# Zynq_power_and_decoupling.net
KiCad netlist of a schematic drawn in Altium Designer
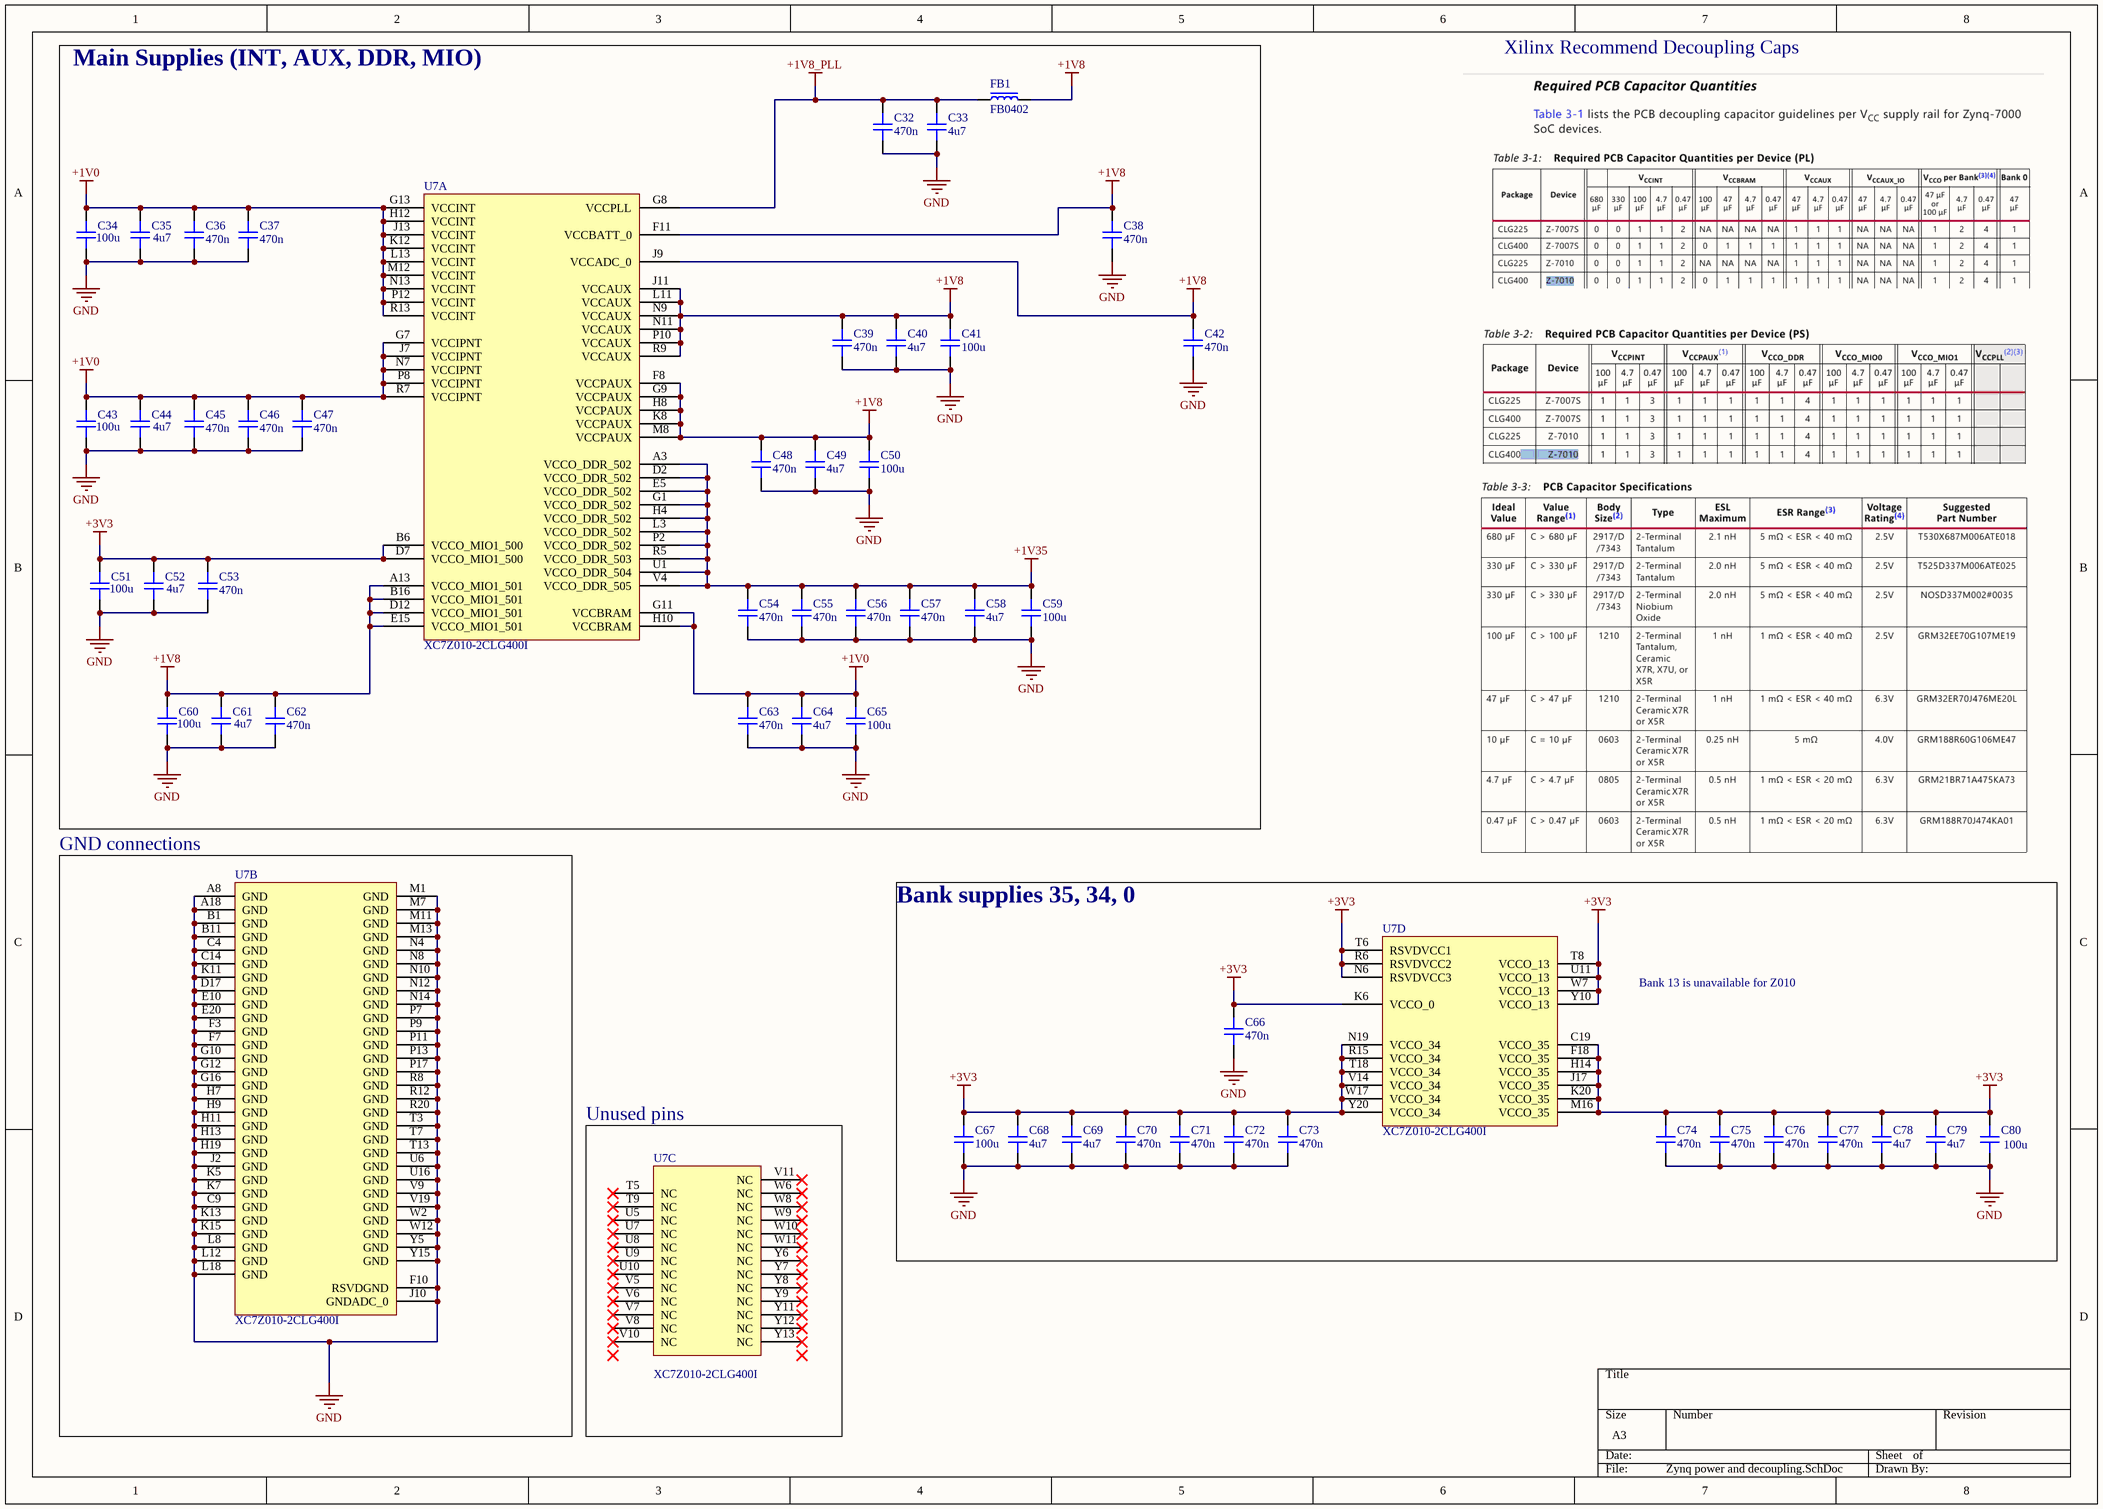
[diagram p0: Zynq power and decoupling.SchDoc]

(export (version "E")
  (design (tool "Eeschema 10.0.6"))
  (components
    (comp (ref "C32")
      (value "470n")
      (footprint "CAP_0201")
      (description "Capacitor SMD 0201")
      (fields (field (name "Comment") "C0201"))
      (libsource (lib "Schematic-Lib-PhilsLab") (part "CAP_0201"))
    )
    (comp (ref "C33")
      (value "4u7")
      (footprint "CAP_0402")
      (description "Capacitor SMD 0402")
      (fields (field (name "Comment") "C0402"))
      (libsource (lib "Schematic-Lib-PhilsLab") (part "CAP_0402"))
    )
    (comp (ref "C34")
      (value "100u")
      (footprint "CAP_1210")
      (description "Capacitor SMD 1210")
      (fields (field (name "Comment") "C1210"))
      (libsource (lib "Schematic-Lib-PhilsLab") (part "CAP_1210"))
    )
    (comp (ref "C35")
      (value "4u7")
      (footprint "CAP_0402")
      (description "Capacitor SMD 0402")
      (fields (field (name "Comment") "C0402"))
      (libsource (lib "Schematic-Lib-PhilsLab") (part "CAP_0402"))
    )
    (comp (ref "C36")
      (value "470n")
      (footprint "CAP_0201")
      (description "Capacitor SMD 0201")
      (fields (field (name "Comment") "C0201"))
      (libsource (lib "Schematic-Lib-PhilsLab") (part "CAP_0201"))
    )
    (comp (ref "C37")
      (value "470n")
      (footprint "CAP_0201")
      (description "Capacitor SMD 0201")
      (fields (field (name "Comment") "C0201"))
      (libsource (lib "Schematic-Lib-PhilsLab") (part "CAP_0201"))
    )
    (comp (ref "C38")
      (value "470n")
      (footprint "CAP_0201")
      (description "Capacitor SMD 0201")
      (fields (field (name "Comment") "C0201"))
      (libsource (lib "Schematic-Lib-PhilsLab") (part "CAP_0201"))
    )
    (comp (ref "C39")
      (value "470n")
      (footprint "CAP_0201")
      (description "Capacitor SMD 0201")
      (fields (field (name "Comment") "C0201"))
      (libsource (lib "Schematic-Lib-PhilsLab") (part "CAP_0201"))
    )
    (comp (ref "C40")
      (value "4u7")
      (footprint "CAP_0402")
      (description "Capacitor SMD 0402")
      (fields (field (name "Comment") "C0402"))
      (libsource (lib "Schematic-Lib-PhilsLab") (part "CAP_0402"))
    )
    (comp (ref "C41")
      (value "100u")
      (footprint "CAP_1210")
      (description "Capacitor SMD 1210")
      (fields (field (name "Comment") "C1210"))
      (libsource (lib "Schematic-Lib-PhilsLab") (part "CAP_1210"))
    )
    (comp (ref "C42")
      (value "470n")
      (footprint "CAP_0201")
      (description "Capacitor SMD 0201")
      (fields (field (name "Comment") "C0201"))
      (libsource (lib "Schematic-Lib-PhilsLab") (part "CAP_0201"))
    )
    (comp (ref "C43")
      (value "100u")
      (footprint "CAP_1210")
      (description "Capacitor SMD 1210")
      (fields (field (name "Comment") "C1210"))
      (libsource (lib "Schematic-Lib-PhilsLab") (part "CAP_1210"))
    )
    (comp (ref "C44")
      (value "4u7")
      (footprint "CAP_0402")
      (description "Capacitor SMD 0402")
      (fields (field (name "Comment") "C0402"))
      (libsource (lib "Schematic-Lib-PhilsLab") (part "CAP_0402"))
    )
    (comp (ref "C45")
      (value "470n")
      (footprint "CAP_0201")
      (description "Capacitor SMD 0201")
      (fields (field (name "Comment") "C0201"))
      (libsource (lib "Schematic-Lib-PhilsLab") (part "CAP_0201"))
    )
    (comp (ref "C46")
      (value "470n")
      (footprint "CAP_0201")
      (description "Capacitor SMD 0201")
      (fields (field (name "Comment") "C0201"))
      (libsource (lib "Schematic-Lib-PhilsLab") (part "CAP_0201"))
    )
    (comp (ref "C47")
      (value "470n")
      (footprint "CAP_0201")
      (description "Capacitor SMD 0201")
      (fields (field (name "Comment") "C0201"))
      (libsource (lib "Schematic-Lib-PhilsLab") (part "CAP_0201"))
    )
    (comp (ref "C48")
      (value "470n")
      (footprint "CAP_0201")
      (description "Capacitor SMD 0201")
      (fields (field (name "Comment") "C0201"))
      (libsource (lib "Schematic-Lib-PhilsLab") (part "CAP_0201"))
    )
    (comp (ref "C49")
      (value "4u7")
      (footprint "CAP_0402")
      (description "Capacitor SMD 0402")
      (fields (field (name "Comment") "C0402"))
      (libsource (lib "Schematic-Lib-PhilsLab") (part "CAP_0402"))
    )
    (comp (ref "C50")
      (value "100u")
      (footprint "CAP_1210")
      (description "Capacitor SMD 1210")
      (fields (field (name "Comment") "C1210"))
      (libsource (lib "Schematic-Lib-PhilsLab") (part "CAP_1210"))
    )
    (comp (ref "C51")
      (value "100u")
      (footprint "CAP_1210")
      (description "Capacitor SMD 1210")
      (fields (field (name "Comment") "C1210"))
      (libsource (lib "Schematic-Lib-PhilsLab") (part "CAP_1210"))
    )
    (comp (ref "C52")
      (value "4u7")
      (footprint "CAP_0402")
      (description "Capacitor SMD 0402")
      (fields (field (name "Comment") "C0402"))
      (libsource (lib "Schematic-Lib-PhilsLab") (part "CAP_0402"))
    )
    (comp (ref "C53")
      (value "470n")
      (footprint "CAP_0201")
      (description "Capacitor SMD 0201")
      (fields (field (name "Comment") "C0201"))
      (libsource (lib "Schematic-Lib-PhilsLab") (part "CAP_0201"))
    )
    (comp (ref "C54")
      (value "470n")
      (footprint "CAP_0201")
      (description "Capacitor SMD 0201")
      (fields (field (name "Comment") "C0201"))
      (libsource (lib "Schematic-Lib-PhilsLab") (part "CAP_0201"))
    )
    (comp (ref "C55")
      (value "470n")
      (footprint "CAP_0201")
      (description "Capacitor SMD 0201")
      (fields (field (name "Comment") "C0201"))
      (libsource (lib "Schematic-Lib-PhilsLab") (part "CAP_0201"))
    )
    (comp (ref "C56")
      (value "470n")
      (footprint "CAP_0201")
      (description "Capacitor SMD 0201")
      (fields (field (name "Comment") "C0201"))
      (libsource (lib "Schematic-Lib-PhilsLab") (part "CAP_0201"))
    )
    (comp (ref "C57")
      (value "470n")
      (footprint "CAP_0201")
      (description "Capacitor SMD 0201")
      (fields (field (name "Comment") "C0201"))
      (libsource (lib "Schematic-Lib-PhilsLab") (part "CAP_0201"))
    )
    (comp (ref "C58")
      (value "4u7")
      (footprint "CAP_0402")
      (description "Capacitor SMD 0402")
      (fields (field (name "Comment") "C0402"))
      (libsource (lib "Schematic-Lib-PhilsLab") (part "CAP_0402"))
    )
    (comp (ref "C59")
      (value "100u")
      (footprint "CAP_1210")
      (description "Capacitor SMD 1210")
      (fields (field (name "Comment") "C1210"))
      (libsource (lib "Schematic-Lib-PhilsLab") (part "CAP_1210"))
    )
    (comp (ref "C60")
      (value "100u")
      (footprint "CAP_1210")
      (description "Capacitor SMD 1210")
      (fields (field (name "Comment") "C1210"))
      (libsource (lib "Schematic-Lib-PhilsLab") (part "CAP_1210"))
    )
    (comp (ref "C61")
      (value "4u7")
      (footprint "CAP_0402")
      (description "Capacitor SMD 0402")
      (fields (field (name "Comment") "C0402"))
      (libsource (lib "Schematic-Lib-PhilsLab") (part "CAP_0402"))
    )
    (comp (ref "C62")
      (value "470n")
      (footprint "CAP_0201")
      (description "Capacitor SMD 0201")
      (fields (field (name "Comment") "C0201"))
      (libsource (lib "Schematic-Lib-PhilsLab") (part "CAP_0201"))
    )
    (comp (ref "C63")
      (value "470n")
      (footprint "CAP_0201")
      (description "Capacitor SMD 0201")
      (fields (field (name "Comment") "C0201"))
      (libsource (lib "Schematic-Lib-PhilsLab") (part "CAP_0201"))
    )
    (comp (ref "C64")
      (value "4u7")
      (footprint "CAP_0402")
      (description "Capacitor SMD 0402")
      (fields (field (name "Comment") "C0402"))
      (libsource (lib "Schematic-Lib-PhilsLab") (part "CAP_0402"))
    )
    (comp (ref "C65")
      (value "100u")
      (footprint "CAP_1210")
      (description "Capacitor SMD 1210")
      (fields (field (name "Comment") "C1210"))
      (libsource (lib "Schematic-Lib-PhilsLab") (part "CAP_1210"))
    )
    (comp (ref "C66")
      (value "470n")
      (footprint "CAP_0201")
      (description "Capacitor SMD 0201")
      (fields (field (name "Comment") "C0201"))
      (libsource (lib "Schematic-Lib-PhilsLab") (part "CAP_0201"))
    )
    (comp (ref "C67")
      (value "100u")
      (footprint "CAP_1210")
      (description "Capacitor SMD 1210")
      (fields (field (name "Comment") "C1210"))
      (libsource (lib "Schematic-Lib-PhilsLab") (part "CAP_1210"))
    )
    (comp (ref "C68")
      (value "4u7")
      (footprint "CAP_0402")
      (description "Capacitor SMD 0402")
      (fields (field (name "Comment") "C0402"))
      (libsource (lib "Schematic-Lib-PhilsLab") (part "CAP_0402"))
    )
    (comp (ref "C69")
      (value "4u7")
      (footprint "CAP_0402")
      (description "Capacitor SMD 0402")
      (fields (field (name "Comment") "C0402"))
      (libsource (lib "Schematic-Lib-PhilsLab") (part "CAP_0402"))
    )
    (comp (ref "C70")
      (value "470n")
      (footprint "CAP_0201")
      (description "Capacitor SMD 0201")
      (fields (field (name "Comment") "C0201"))
      (libsource (lib "Schematic-Lib-PhilsLab") (part "CAP_0201"))
    )
    (comp (ref "C71")
      (value "470n")
      (footprint "CAP_0201")
      (description "Capacitor SMD 0201")
      (fields (field (name "Comment") "C0201"))
      (libsource (lib "Schematic-Lib-PhilsLab") (part "CAP_0201"))
    )
    (comp (ref "C72")
      (value "470n")
      (footprint "CAP_0201")
      (description "Capacitor SMD 0201")
      (fields (field (name "Comment") "C0201"))
      (libsource (lib "Schematic-Lib-PhilsLab") (part "CAP_0201"))
    )
    (comp (ref "C73")
      (value "470n")
      (footprint "CAP_0201")
      (description "Capacitor SMD 0201")
      (fields (field (name "Comment") "C0201"))
      (libsource (lib "Schematic-Lib-PhilsLab") (part "CAP_0201"))
    )
    (comp (ref "C74")
      (value "470n")
      (footprint "CAP_0201")
      (description "Capacitor SMD 0201")
      (fields (field (name "Comment") "C0201"))
      (libsource (lib "Schematic-Lib-PhilsLab") (part "CAP_0201"))
    )
    (comp (ref "C75")
      (value "470n")
      (footprint "CAP_0201")
      (description "Capacitor SMD 0201")
      (fields (field (name "Comment") "C0201"))
      (libsource (lib "Schematic-Lib-PhilsLab") (part "CAP_0201"))
    )
    (comp (ref "C76")
      (value "470n")
      (footprint "CAP_0201")
      (description "Capacitor SMD 0201")
      (fields (field (name "Comment") "C0201"))
      (libsource (lib "Schematic-Lib-PhilsLab") (part "CAP_0201"))
    )
    (comp (ref "C77")
      (value "470n")
      (footprint "CAP_0201")
      (description "Capacitor SMD 0201")
      (fields (field (name "Comment") "C0201"))
      (libsource (lib "Schematic-Lib-PhilsLab") (part "CAP_0201"))
    )
    (comp (ref "C78")
      (value "4u7")
      (footprint "CAP_0402")
      (description "Capacitor SMD 0402")
      (fields (field (name "Comment") "C0402"))
      (libsource (lib "Schematic-Lib-PhilsLab") (part "CAP_0402"))
    )
    (comp (ref "C79")
      (value "4u7")
      (footprint "CAP_0402")
      (description "Capacitor SMD 0402")
      (fields (field (name "Comment") "C0402"))
      (libsource (lib "Schematic-Lib-PhilsLab") (part "CAP_0402"))
    )
    (comp (ref "C80")
      (value "100u")
      (footprint "CAP_1210")
      (description "Capacitor SMD 1210")
      (fields (field (name "Comment") "C1210"))
      (libsource (lib "Schematic-Lib-PhilsLab") (part "CAP_1210"))
    )
    (comp (ref "FB1")
      (value "FB0402")
      (footprint "FB_0402")
      (description "Ferrite Bead SMD 0402")
      (libsource (lib "Schematic-Lib-PhilsLab") (part "FB_0402"))
    )
    (comp (ref "U7")
      (value "XC7Z010-2CLG400I")
      (footprint "BGA400C80P20X20_1700X1700X160N")
      (libsource (lib "Zynq_SOM") (part "XC7Z010-2CLG400I"))
    )
  )
  (nets
    (net (code "1") (name "+1V0") (class "Default")
      (node (ref "C34") (pin "2") (pinfunction "2_2") (pintype "passive"))
      (node (ref "C35") (pin "2") (pinfunction "2_2") (pintype "passive"))
      (node (ref "C36") (pin "2") (pinfunction "2_2") (pintype "passive"))
      (node (ref "C37") (pin "2") (pinfunction "2_2") (pintype "passive"))
      (node (ref "C43") (pin "2") (pinfunction "2_2") (pintype "passive"))
      (node (ref "C44") (pin "2") (pinfunction "2_2") (pintype "passive"))
      (node (ref "C45") (pin "2") (pinfunction "2_2") (pintype "passive"))
      (node (ref "C46") (pin "2") (pinfunction "2_2") (pintype "passive"))
      (node (ref "C47") (pin "2") (pinfunction "2_2") (pintype "passive"))
      (node (ref "C63") (pin "2") (pinfunction "2_2") (pintype "passive"))
      (node (ref "C64") (pin "2") (pinfunction "2_2") (pintype "passive"))
      (node (ref "C65") (pin "2") (pinfunction "2_2") (pintype "passive"))
      (node (ref "U7") (pin "G11") (pinfunction "VCCBRAM_G11") (pintype "passive"))
      (node (ref "U7") (pin "G13") (pinfunction "VCCINT_G13") (pintype "passive"))
      (node (ref "U7") (pin "G7") (pinfunction "VCCIPNT_G7") (pintype "passive"))
      (node (ref "U7") (pin "H10") (pinfunction "VCCBRAM_H10") (pintype "passive"))
      (node (ref "U7") (pin "H12") (pinfunction "VCCINT_H12") (pintype "passive"))
      (node (ref "U7") (pin "J13") (pinfunction "VCCINT_J13") (pintype "passive"))
      (node (ref "U7") (pin "J7") (pinfunction "VCCIPNT_J7") (pintype "passive"))
      (node (ref "U7") (pin "K12") (pinfunction "VCCINT_K12") (pintype "passive"))
      (node (ref "U7") (pin "L13") (pinfunction "VCCINT_L13") (pintype "passive"))
      (node (ref "U7") (pin "M12") (pinfunction "VCCINT_M12") (pintype "passive"))
      (node (ref "U7") (pin "N13") (pinfunction "VCCINT_N13") (pintype "passive"))
      (node (ref "U7") (pin "N7") (pinfunction "VCCIPNT_N7") (pintype "passive"))
      (node (ref "U7") (pin "P12") (pinfunction "VCCINT_P12") (pintype "passive"))
      (node (ref "U7") (pin "P8") (pinfunction "VCCIPNT_P8") (pintype "passive"))
      (node (ref "U7") (pin "R13") (pinfunction "VCCINT_R13") (pintype "passive"))
      (node (ref "U7") (pin "R7") (pinfunction "VCCIPNT_R7") (pintype "passive"))
    )
    (net (code "2") (name "+1V8") (class "Default")
      (node (ref "C38") (pin "2") (pinfunction "2_2") (pintype "passive"))
      (node (ref "C39") (pin "2") (pinfunction "2_2") (pintype "passive"))
      (node (ref "C40") (pin "2") (pinfunction "2_2") (pintype "passive"))
      (node (ref "C41") (pin "2") (pinfunction "2_2") (pintype "passive"))
      (node (ref "C42") (pin "2") (pinfunction "2_2") (pintype "passive"))
      (node (ref "C48") (pin "2") (pinfunction "2_2") (pintype "passive"))
      (node (ref "C49") (pin "2") (pinfunction "2_2") (pintype "passive"))
      (node (ref "C50") (pin "2") (pinfunction "2_2") (pintype "passive"))
      (node (ref "C60") (pin "2") (pinfunction "2_2") (pintype "passive"))
      (node (ref "C61") (pin "2") (pinfunction "2_2") (pintype "passive"))
      (node (ref "C62") (pin "2") (pinfunction "2_2") (pintype "passive"))
      (node (ref "FB1") (pin "2") (pinfunction "2_2") (pintype "passive"))
      (node (ref "U7") (pin "A13") (pinfunction "VCCO_MIO1_501_A13") (pintype "passive"))
      (node (ref "U7") (pin "B16") (pinfunction "VCCO_MIO1_501_B16") (pintype "passive"))
      (node (ref "U7") (pin "D12") (pinfunction "VCCO_MIO1_501_D12") (pintype "passive"))
      (node (ref "U7") (pin "E15") (pinfunction "VCCO_MIO1_501_E15") (pintype "passive"))
      (node (ref "U7") (pin "F11") (pinfunction "VCCBATT_0_F11") (pintype "passive"))
      (node (ref "U7") (pin "F8") (pinfunction "VCCPAUX_F8") (pintype "passive"))
      (node (ref "U7") (pin "G9") (pinfunction "VCCPAUX_G9") (pintype "passive"))
      (node (ref "U7") (pin "H8") (pinfunction "VCCPAUX_H8") (pintype "passive"))
      (node (ref "U7") (pin "J11") (pinfunction "VCCAUX_J11") (pintype "passive"))
      (node (ref "U7") (pin "J9") (pinfunction "VCCADC_0_J9") (pintype "passive"))
      (node (ref "U7") (pin "K8") (pinfunction "VCCPAUX_K8") (pintype "passive"))
      (node (ref "U7") (pin "L11") (pinfunction "VCCAUX_L11") (pintype "passive"))
      (node (ref "U7") (pin "M8") (pinfunction "VCCPAUX_M8") (pintype "passive"))
      (node (ref "U7") (pin "N11") (pinfunction "VCCAUX_N11") (pintype "passive"))
      (node (ref "U7") (pin "N9") (pinfunction "VCCAUX_N9") (pintype "passive"))
      (node (ref "U7") (pin "P10") (pinfunction "VCCAUX_P10") (pintype "passive"))
      (node (ref "U7") (pin "R9") (pinfunction "VCCAUX_R9") (pintype "passive"))
    )
    (net (code "3") (name "+1V8_PLL") (class "Default")
      (node (ref "C32") (pin "2") (pinfunction "2_2") (pintype "passive"))
      (node (ref "C33") (pin "2") (pinfunction "2_2") (pintype "passive"))
      (node (ref "FB1") (pin "1") (pinfunction "1_1") (pintype "passive"))
      (node (ref "U7") (pin "G8") (pinfunction "VCCPLL_G8") (pintype "passive"))
    )
    (net (code "4") (name "+1V35") (class "Default")
      (node (ref "C54") (pin "2") (pinfunction "2_2") (pintype "passive"))
      (node (ref "C55") (pin "2") (pinfunction "2_2") (pintype "passive"))
      (node (ref "C56") (pin "2") (pinfunction "2_2") (pintype "passive"))
      (node (ref "C57") (pin "2") (pinfunction "2_2") (pintype "passive"))
      (node (ref "C58") (pin "2") (pinfunction "2_2") (pintype "passive"))
      (node (ref "C59") (pin "2") (pinfunction "2_2") (pintype "passive"))
      (node (ref "U7") (pin "A3") (pinfunction "VCCO_DDR_502_A3") (pintype "passive"))
      (node (ref "U7") (pin "D2") (pinfunction "VCCO_DDR_502_D2") (pintype "passive"))
      (node (ref "U7") (pin "E5") (pinfunction "VCCO_DDR_502_E5") (pintype "passive"))
      (node (ref "U7") (pin "G1") (pinfunction "VCCO_DDR_502_G1") (pintype "passive"))
      (node (ref "U7") (pin "H4") (pinfunction "VCCO_DDR_502_H4") (pintype "passive"))
      (node (ref "U7") (pin "L3") (pinfunction "VCCO_DDR_502_L3") (pintype "passive"))
      (node (ref "U7") (pin "P2") (pinfunction "VCCO_DDR_502_P2") (pintype "passive"))
      (node (ref "U7") (pin "R5") (pinfunction "VCCO_DDR_503_R5") (pintype "passive"))
      (node (ref "U7") (pin "U1") (pinfunction "VCCO_DDR_504_U1") (pintype "passive"))
      (node (ref "U7") (pin "V4") (pinfunction "VCCO_DDR_505_V4") (pintype "passive"))
    )
    (net (code "5") (name "+3V3") (class "Default")
      (node (ref "C51") (pin "2") (pinfunction "2_2") (pintype "passive"))
      (node (ref "C52") (pin "2") (pinfunction "2_2") (pintype "passive"))
      (node (ref "C53") (pin "2") (pinfunction "2_2") (pintype "passive"))
      (node (ref "C66") (pin "2") (pinfunction "2_2") (pintype "passive"))
      (node (ref "C67") (pin "2") (pinfunction "2_2") (pintype "passive"))
      (node (ref "C68") (pin "2") (pinfunction "2_2") (pintype "passive"))
      (node (ref "C69") (pin "2") (pinfunction "2_2") (pintype "passive"))
      (node (ref "C70") (pin "2") (pinfunction "2_2") (pintype "passive"))
      (node (ref "C71") (pin "2") (pinfunction "2_2") (pintype "passive"))
      (node (ref "C72") (pin "2") (pinfunction "2_2") (pintype "passive"))
      (node (ref "C73") (pin "2") (pinfunction "2_2") (pintype "passive"))
      (node (ref "C74") (pin "2") (pinfunction "2_2") (pintype "passive"))
      (node (ref "C75") (pin "2") (pinfunction "2_2") (pintype "passive"))
      (node (ref "C76") (pin "2") (pinfunction "2_2") (pintype "passive"))
      (node (ref "C77") (pin "2") (pinfunction "2_2") (pintype "passive"))
      (node (ref "C78") (pin "2") (pinfunction "2_2") (pintype "passive"))
      (node (ref "C79") (pin "2") (pinfunction "2_2") (pintype "passive"))
      (node (ref "C80") (pin "2") (pinfunction "2_2") (pintype "passive"))
      (node (ref "U7") (pin "B6") (pinfunction "VCCO_MIO1_500_B6") (pintype "passive"))
      (node (ref "U7") (pin "C19") (pinfunction "VCCO_35_C19") (pintype "passive"))
      (node (ref "U7") (pin "D7") (pinfunction "VCCO_MIO1_500_D7") (pintype "passive"))
      (node (ref "U7") (pin "F18") (pinfunction "VCCO_35_F18") (pintype "passive"))
      (node (ref "U7") (pin "H14") (pinfunction "VCCO_35_H14") (pintype "passive"))
      (node (ref "U7") (pin "J17") (pinfunction "VCCO_35_J17") (pintype "passive"))
      (node (ref "U7") (pin "K20") (pinfunction "VCCO_35_K20") (pintype "passive"))
      (node (ref "U7") (pin "K6") (pinfunction "VCCO_0_K6") (pintype "passive"))
      (node (ref "U7") (pin "M16") (pinfunction "VCCO_35_M16") (pintype "passive"))
      (node (ref "U7") (pin "N19") (pinfunction "VCCO_34_N19") (pintype "passive"))
      (node (ref "U7") (pin "N6") (pinfunction "RSVDVCC3_N6") (pintype "passive"))
      (node (ref "U7") (pin "R15") (pinfunction "VCCO_34_R15") (pintype "passive"))
      (node (ref "U7") (pin "R6") (pinfunction "RSVDVCC2_R6") (pintype "passive"))
      (node (ref "U7") (pin "T18") (pinfunction "VCCO_34_T18") (pintype "passive"))
      (node (ref "U7") (pin "T6") (pinfunction "RSVDVCC1_T6") (pintype "passive"))
      (node (ref "U7") (pin "T8") (pinfunction "VCCO_13_T8") (pintype "passive"))
      (node (ref "U7") (pin "U11") (pinfunction "VCCO_13_U11") (pintype "passive"))
      (node (ref "U7") (pin "V14") (pinfunction "VCCO_34_V14") (pintype "passive"))
      (node (ref "U7") (pin "W17") (pinfunction "VCCO_34_W17") (pintype "passive"))
      (node (ref "U7") (pin "W7") (pinfunction "VCCO_13_W7") (pintype "passive"))
      (node (ref "U7") (pin "Y10") (pinfunction "VCCO_13_Y10") (pintype "passive"))
      (node (ref "U7") (pin "Y20") (pinfunction "VCCO_34_Y20") (pintype "passive"))
    )
    (net (code "6") (name "GND") (class "Default")
      (node (ref "C32") (pin "1") (pinfunction "1_1") (pintype "passive"))
      (node (ref "C33") (pin "1") (pinfunction "1_1") (pintype "passive"))
      (node (ref "C34") (pin "1") (pinfunction "1_1") (pintype "passive"))
      (node (ref "C35") (pin "1") (pinfunction "1_1") (pintype "passive"))
      (node (ref "C36") (pin "1") (pinfunction "1_1") (pintype "passive"))
      (node (ref "C37") (pin "1") (pinfunction "1_1") (pintype "passive"))
      (node (ref "C38") (pin "1") (pinfunction "1_1") (pintype "passive"))
      (node (ref "C39") (pin "1") (pinfunction "1_1") (pintype "passive"))
      (node (ref "C40") (pin "1") (pinfunction "1_1") (pintype "passive"))
      (node (ref "C41") (pin "1") (pinfunction "1_1") (pintype "passive"))
      (node (ref "C42") (pin "1") (pinfunction "1_1") (pintype "passive"))
      (node (ref "C43") (pin "1") (pinfunction "1_1") (pintype "passive"))
      (node (ref "C44") (pin "1") (pinfunction "1_1") (pintype "passive"))
      (node (ref "C45") (pin "1") (pinfunction "1_1") (pintype "passive"))
      (node (ref "C46") (pin "1") (pinfunction "1_1") (pintype "passive"))
      (node (ref "C47") (pin "1") (pinfunction "1_1") (pintype "passive"))
      (node (ref "C48") (pin "1") (pinfunction "1_1") (pintype "passive"))
      (node (ref "C49") (pin "1") (pinfunction "1_1") (pintype "passive"))
      (node (ref "C50") (pin "1") (pinfunction "1_1") (pintype "passive"))
      (node (ref "C51") (pin "1") (pinfunction "1_1") (pintype "passive"))
      (node (ref "C52") (pin "1") (pinfunction "1_1") (pintype "passive"))
      (node (ref "C53") (pin "1") (pinfunction "1_1") (pintype "passive"))
      (node (ref "C54") (pin "1") (pinfunction "1_1") (pintype "passive"))
      (node (ref "C55") (pin "1") (pinfunction "1_1") (pintype "passive"))
      (node (ref "C56") (pin "1") (pinfunction "1_1") (pintype "passive"))
      (node (ref "C57") (pin "1") (pinfunction "1_1") (pintype "passive"))
      (node (ref "C58") (pin "1") (pinfunction "1_1") (pintype "passive"))
      (node (ref "C59") (pin "1") (pinfunction "1_1") (pintype "passive"))
      (node (ref "C60") (pin "1") (pinfunction "1_1") (pintype "passive"))
      (node (ref "C61") (pin "1") (pinfunction "1_1") (pintype "passive"))
      (node (ref "C62") (pin "1") (pinfunction "1_1") (pintype "passive"))
      (node (ref "C63") (pin "1") (pinfunction "1_1") (pintype "passive"))
      (node (ref "C64") (pin "1") (pinfunction "1_1") (pintype "passive"))
      (node (ref "C65") (pin "1") (pinfunction "1_1") (pintype "passive"))
      (node (ref "C66") (pin "1") (pinfunction "1_1") (pintype "passive"))
      (node (ref "C67") (pin "1") (pinfunction "1_1") (pintype "passive"))
      (node (ref "C68") (pin "1") (pinfunction "1_1") (pintype "passive"))
      (node (ref "C69") (pin "1") (pinfunction "1_1") (pintype "passive"))
      (node (ref "C70") (pin "1") (pinfunction "1_1") (pintype "passive"))
      (node (ref "C71") (pin "1") (pinfunction "1_1") (pintype "passive"))
      (node (ref "C72") (pin "1") (pinfunction "1_1") (pintype "passive"))
      (node (ref "C73") (pin "1") (pinfunction "1_1") (pintype "passive"))
      (node (ref "C74") (pin "1") (pinfunction "1_1") (pintype "passive"))
      (node (ref "C75") (pin "1") (pinfunction "1_1") (pintype "passive"))
      (node (ref "C76") (pin "1") (pinfunction "1_1") (pintype "passive"))
      (node (ref "C77") (pin "1") (pinfunction "1_1") (pintype "passive"))
      (node (ref "C78") (pin "1") (pinfunction "1_1") (pintype "passive"))
      (node (ref "C79") (pin "1") (pinfunction "1_1") (pintype "passive"))
      (node (ref "C80") (pin "1") (pinfunction "1_1") (pintype "passive"))
      (node (ref "U7") (pin "A18") (pinfunction "GND_A18") (pintype "passive"))
      (node (ref "U7") (pin "A8") (pinfunction "GND_A8") (pintype "passive"))
      (node (ref "U7") (pin "B1") (pinfunction "GND_B1") (pintype "passive"))
      (node (ref "U7") (pin "B11") (pinfunction "GND_B11") (pintype "passive"))
      (node (ref "U7") (pin "C14") (pinfunction "GND_C14") (pintype "passive"))
      (node (ref "U7") (pin "C4") (pinfunction "GND_C4") (pintype "passive"))
      (node (ref "U7") (pin "C9") (pinfunction "GND_C9") (pintype "passive"))
      (node (ref "U7") (pin "D17") (pinfunction "GND_D17") (pintype "passive"))
      (node (ref "U7") (pin "E10") (pinfunction "GND_E10") (pintype "passive"))
      (node (ref "U7") (pin "E20") (pinfunction "GND_E20") (pintype "passive"))
      (node (ref "U7") (pin "F10") (pinfunction "RSVDGND_F10") (pintype "passive"))
      (node (ref "U7") (pin "F3") (pinfunction "GND_F3") (pintype "passive"))
      (node (ref "U7") (pin "F7") (pinfunction "GND_F7") (pintype "passive"))
      (node (ref "U7") (pin "G10") (pinfunction "GND_G10") (pintype "passive"))
      (node (ref "U7") (pin "G12") (pinfunction "GND_G12") (pintype "passive"))
      (node (ref "U7") (pin "G16") (pinfunction "GND_G16") (pintype "passive"))
      (node (ref "U7") (pin "H11") (pinfunction "GND_H11") (pintype "passive"))
      (node (ref "U7") (pin "H13") (pinfunction "GND_H13") (pintype "passive"))
      (node (ref "U7") (pin "H19") (pinfunction "GND_H19") (pintype "passive"))
      (node (ref "U7") (pin "H7") (pinfunction "GND_H7") (pintype "passive"))
      (node (ref "U7") (pin "H9") (pinfunction "GND_H9") (pintype "passive"))
      (node (ref "U7") (pin "J10") (pinfunction "GNDADC_0_J10") (pintype "passive"))
      (node (ref "U7") (pin "J2") (pinfunction "GND_J2") (pintype "passive"))
      (node (ref "U7") (pin "K11") (pinfunction "GND_K11") (pintype "passive"))
      (node (ref "U7") (pin "K13") (pinfunction "GND_K13") (pintype "passive"))
      (node (ref "U7") (pin "K15") (pinfunction "GND_K15") (pintype "passive"))
      (node (ref "U7") (pin "K5") (pinfunction "GND_K5") (pintype "passive"))
      (node (ref "U7") (pin "K7") (pinfunction "GND_K7") (pintype "passive"))
      (node (ref "U7") (pin "L12") (pinfunction "GND_L12") (pintype "passive"))
      (node (ref "U7") (pin "L18") (pinfunction "GND_L18") (pintype "passive"))
      (node (ref "U7") (pin "L8") (pinfunction "GND_L8") (pintype "passive"))
      (node (ref "U7") (pin "M1") (pinfunction "GND_M1") (pintype "passive"))
      (node (ref "U7") (pin "M11") (pinfunction "GND_M11") (pintype "passive"))
      (node (ref "U7") (pin "M13") (pinfunction "GND_M13") (pintype "passive"))
      (node (ref "U7") (pin "M7") (pinfunction "GND_M7") (pintype "passive"))
      (node (ref "U7") (pin "N10") (pinfunction "GND_N10") (pintype "passive"))
      (node (ref "U7") (pin "N12") (pinfunction "GND_N12") (pintype "passive"))
      (node (ref "U7") (pin "N14") (pinfunction "GND_N14") (pintype "passive"))
      (node (ref "U7") (pin "N4") (pinfunction "GND_N4") (pintype "passive"))
      (node (ref "U7") (pin "N8") (pinfunction "GND_N8") (pintype "passive"))
      (node (ref "U7") (pin "P11") (pinfunction "GND_P11") (pintype "passive"))
      (node (ref "U7") (pin "P13") (pinfunction "GND_P13") (pintype "passive"))
      (node (ref "U7") (pin "P17") (pinfunction "GND_P17") (pintype "passive"))
      (node (ref "U7") (pin "P7") (pinfunction "GND_P7") (pintype "passive"))
      (node (ref "U7") (pin "P9") (pinfunction "GND_P9") (pintype "passive"))
      (node (ref "U7") (pin "R12") (pinfunction "GND_R12") (pintype "passive"))
      (node (ref "U7") (pin "R20") (pinfunction "GND_R20") (pintype "passive"))
      (node (ref "U7") (pin "R8") (pinfunction "GND_R8") (pintype "passive"))
      (node (ref "U7") (pin "T13") (pinfunction "GND_T13") (pintype "passive"))
      (node (ref "U7") (pin "T3") (pinfunction "GND_T3") (pintype "passive"))
      (node (ref "U7") (pin "T7") (pinfunction "GND_T7") (pintype "passive"))
      (node (ref "U7") (pin "U16") (pinfunction "GND_U16") (pintype "passive"))
      (node (ref "U7") (pin "U6") (pinfunction "GND_U6") (pintype "passive"))
      (node (ref "U7") (pin "V19") (pinfunction "GND_V19") (pintype "passive"))
      (node (ref "U7") (pin "V9") (pinfunction "GND_V9") (pintype "passive"))
      (node (ref "U7") (pin "W12") (pinfunction "GND_W12") (pintype "passive"))
      (node (ref "U7") (pin "W2") (pinfunction "GND_W2") (pintype "passive"))
      (node (ref "U7") (pin "Y15") (pinfunction "GND_Y15") (pintype "passive"))
      (node (ref "U7") (pin "Y5") (pinfunction "GND_Y5") (pintype "passive"))
    )
    (net (code "7") (name "unconnected-(U7C-NC-PadT5)") (class "Default")
      (node (ref "U7") (pin "T5") (pinfunction "NC_T5") (pintype "passive+no_connect"))
    )
    (net (code "8") (name "unconnected-(U7C-NC-PadT9)") (class "Default")
      (node (ref "U7") (pin "T9") (pinfunction "NC_T9") (pintype "passive+no_connect"))
    )
    (net (code "9") (name "unconnected-(U7C-NC-PadU5)") (class "Default")
      (node (ref "U7") (pin "U5") (pinfunction "NC_U5") (pintype "passive+no_connect"))
    )
    (net (code "10") (name "unconnected-(U7C-NC-PadU7)") (class "Default")
      (node (ref "U7") (pin "U7") (pinfunction "NC_U7") (pintype "passive+no_connect"))
    )
    (net (code "11") (name "unconnected-(U7C-NC-PadU8)") (class "Default")
      (node (ref "U7") (pin "U8") (pinfunction "NC_U8") (pintype "passive+no_connect"))
    )
    (net (code "12") (name "unconnected-(U7C-NC-PadU9)") (class "Default")
      (node (ref "U7") (pin "U9") (pinfunction "NC_U9") (pintype "passive+no_connect"))
    )
    (net (code "13") (name "unconnected-(U7C-NC-PadU10)") (class "Default")
      (node (ref "U7") (pin "U10") (pinfunction "NC_U10") (pintype "passive+no_connect"))
    )
    (net (code "14") (name "unconnected-(U7C-NC-PadV5)") (class "Default")
      (node (ref "U7") (pin "V5") (pinfunction "NC_V5") (pintype "passive+no_connect"))
    )
    (net (code "15") (name "unconnected-(U7C-NC-PadV6)") (class "Default")
      (node (ref "U7") (pin "V6") (pinfunction "NC_V6") (pintype "passive+no_connect"))
    )
    (net (code "16") (name "unconnected-(U7C-NC-PadV7)") (class "Default")
      (node (ref "U7") (pin "V7") (pinfunction "NC_V7") (pintype "passive+no_connect"))
    )
    (net (code "17") (name "unconnected-(U7C-NC-PadV8)") (class "Default")
      (node (ref "U7") (pin "V8") (pinfunction "NC_V8") (pintype "passive+no_connect"))
    )
    (net (code "18") (name "unconnected-(U7C-NC-PadV10)") (class "Default")
      (node (ref "U7") (pin "V10") (pinfunction "NC_V10") (pintype "passive+no_connect"))
    )
    (net (code "19") (name "unconnected-(U7C-NC-PadV11)") (class "Default")
      (node (ref "U7") (pin "V11") (pinfunction "NC_V11") (pintype "passive+no_connect"))
    )
    (net (code "20") (name "unconnected-(U7C-NC-PadW6)") (class "Default")
      (node (ref "U7") (pin "W6") (pinfunction "NC_W6") (pintype "passive+no_connect"))
    )
    (net (code "21") (name "unconnected-(U7C-NC-PadW8)") (class "Default")
      (node (ref "U7") (pin "W8") (pinfunction "NC_W8") (pintype "passive+no_connect"))
    )
    (net (code "22") (name "unconnected-(U7C-NC-PadW9)") (class "Default")
      (node (ref "U7") (pin "W9") (pinfunction "NC_W9") (pintype "passive+no_connect"))
    )
    (net (code "23") (name "unconnected-(U7C-NC-PadW10)") (class "Default")
      (node (ref "U7") (pin "W10") (pinfunction "NC_W10") (pintype "passive+no_connect"))
    )
    (net (code "24") (name "unconnected-(U7C-NC-PadW11)") (class "Default")
      (node (ref "U7") (pin "W11") (pinfunction "NC_W11") (pintype "passive+no_connect"))
    )
    (net (code "25") (name "unconnected-(U7C-NC-PadY6)") (class "Default")
      (node (ref "U7") (pin "Y6") (pinfunction "NC_Y6") (pintype "passive+no_connect"))
    )
    (net (code "26") (name "unconnected-(U7C-NC-PadY7)") (class "Default")
      (node (ref "U7") (pin "Y7") (pinfunction "NC_Y7") (pintype "passive+no_connect"))
    )
    (net (code "27") (name "unconnected-(U7C-NC-PadY8)") (class "Default")
      (node (ref "U7") (pin "Y8") (pinfunction "NC_Y8") (pintype "passive+no_connect"))
    )
    (net (code "28") (name "unconnected-(U7C-NC-PadY9)") (class "Default")
      (node (ref "U7") (pin "Y9") (pinfunction "NC_Y9") (pintype "passive+no_connect"))
    )
    (net (code "29") (name "unconnected-(U7C-NC-PadY11)") (class "Default")
      (node (ref "U7") (pin "Y11") (pinfunction "NC_Y11") (pintype "passive+no_connect"))
    )
    (net (code "30") (name "unconnected-(U7C-NC-PadY12)") (class "Default")
      (node (ref "U7") (pin "Y12") (pinfunction "NC_Y12") (pintype "passive+no_connect"))
    )
    (net (code "31") (name "unconnected-(U7C-NC-PadY13)") (class "Default")
      (node (ref "U7") (pin "Y13") (pinfunction "NC_Y13") (pintype "passive+no_connect"))
    )
  )
)
